# robot7.net
KiCad netlist of a schematic drawn in EAGLE
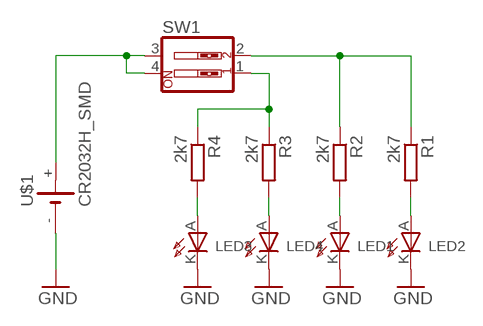
[diagram p0: schematic, sheet 1]

(export (version "E")
  (design (tool "Eeschema 10.0.6"))
  (components
    (comp (ref "LED1")
      (value "LEDREAR")
      (footprint "eagle-import:3MM_REAR")
      (libsource (lib "eagle-import") (part "LEDREAR"))
    )
    (comp (ref "LED2")
      (value "LEDREAR")
      (footprint "eagle-import:3MM_REAR")
      (libsource (lib "eagle-import") (part "LEDREAR"))
    )
    (comp (ref "LED3")
      (value "LED3MMH")
      (footprint "eagle-import:3MM_H")
      (libsource (lib "eagle-import") (part "LED3MMH"))
    )
    (comp (ref "LED4")
      (value "LED3MMH")
      (footprint "eagle-import:3MM_H")
      (libsource (lib "eagle-import") (part "LED3MMH"))
    )
    (comp (ref "R1")
      (value "2k7")
      (footprint "eagle-import:0204_7")
      (libsource (lib "eagle-import") (part "R-EU_0204/7"))
    )
    (comp (ref "R2")
      (value "2k7")
      (footprint "eagle-import:0204_7")
      (libsource (lib "eagle-import") (part "R-EU_0204/7"))
    )
    (comp (ref "R3")
      (value "2k7")
      (footprint "eagle-import:0204_7")
      (libsource (lib "eagle-import") (part "R-EU_0204/7"))
    )
    (comp (ref "R4")
      (value "2k7")
      (footprint "eagle-import:0204_7")
      (libsource (lib "eagle-import") (part "R-EU_0204/7"))
    )
    (comp (ref "SW1")
      (value "SW_DIP-2")
      (footprint "eagle-import:EDG-02")
      (libsource (lib "eagle-import") (part "SW_DIP-2"))
    )
    (comp (ref "U$1")
      (value "CR2032H_SMD")
      (footprint "eagle-import:CR2032H_SMD")
      (libsource (lib "eagle-import") (part "CR2032H_SMD"))
    )
  )
  (nets
    (net (code "1") (name "GND") (class "Default")
      (node (ref "LED1") (pin "K") (pinfunction "K_K") (pintype "passive"))
      (node (ref "LED2") (pin "K") (pinfunction "K_K") (pintype "passive"))
      (node (ref "LED3") (pin "K") (pinfunction "K_K") (pintype "passive"))
      (node (ref "LED4") (pin "K") (pinfunction "K_K") (pintype "passive"))
      (node (ref "U$1") (pin "-") (pinfunction "-_-") (pintype "passive"))
    )
    (net (code "2") (name "Net-(LED1-PadA)") (class "Default")
      (node (ref "LED1") (pin "A") (pinfunction "A_A") (pintype "passive"))
      (node (ref "R2") (pin "2") (pinfunction "2_2") (pintype "passive"))
    )
    (net (code "3") (name "Net-(LED2-PadA)") (class "Default")
      (node (ref "LED2") (pin "A") (pinfunction "A_A") (pintype "passive"))
      (node (ref "R1") (pin "2") (pinfunction "2_2") (pintype "passive"))
    )
    (net (code "4") (name "Net-(LED3-PadA)") (class "Default")
      (node (ref "LED3") (pin "A") (pinfunction "A_A") (pintype "passive"))
      (node (ref "R4") (pin "2") (pinfunction "2_2") (pintype "passive"))
    )
    (net (code "5") (name "Net-(LED4-PadA)") (class "Default")
      (node (ref "LED4") (pin "A") (pinfunction "A_A") (pintype "passive"))
      (node (ref "R3") (pin "2") (pinfunction "2_2") (pintype "passive"))
    )
    (net (code "6") (name "Net-(R1-Pad1)") (class "Default")
      (node (ref "R1") (pin "1") (pinfunction "1_1") (pintype "passive"))
      (node (ref "R2") (pin "1") (pinfunction "1_1") (pintype "passive"))
      (node (ref "SW1") (pin "2") (pinfunction "2_2") (pintype "passive"))
    )
    (net (code "7") (name "Net-(R3-Pad1)") (class "Default")
      (node (ref "R3") (pin "1") (pinfunction "1_1") (pintype "passive"))
      (node (ref "R4") (pin "1") (pinfunction "1_1") (pintype "passive"))
      (node (ref "SW1") (pin "1") (pinfunction "1_1") (pintype "passive"))
    )
    (net (code "8") (name "Net-(SW1-Pad3)") (class "Default")
      (node (ref "SW1") (pin "3") (pinfunction "3_3") (pintype "passive"))
      (node (ref "SW1") (pin "4") (pinfunction "4_4") (pintype "passive"))
      (node (ref "U$1") (pin "+") (pinfunction "+_+") (pintype "passive"))
    )
  )
)
